# 13_Clocks.net
KiCad netlist of a schematic drawn in Altium Designer
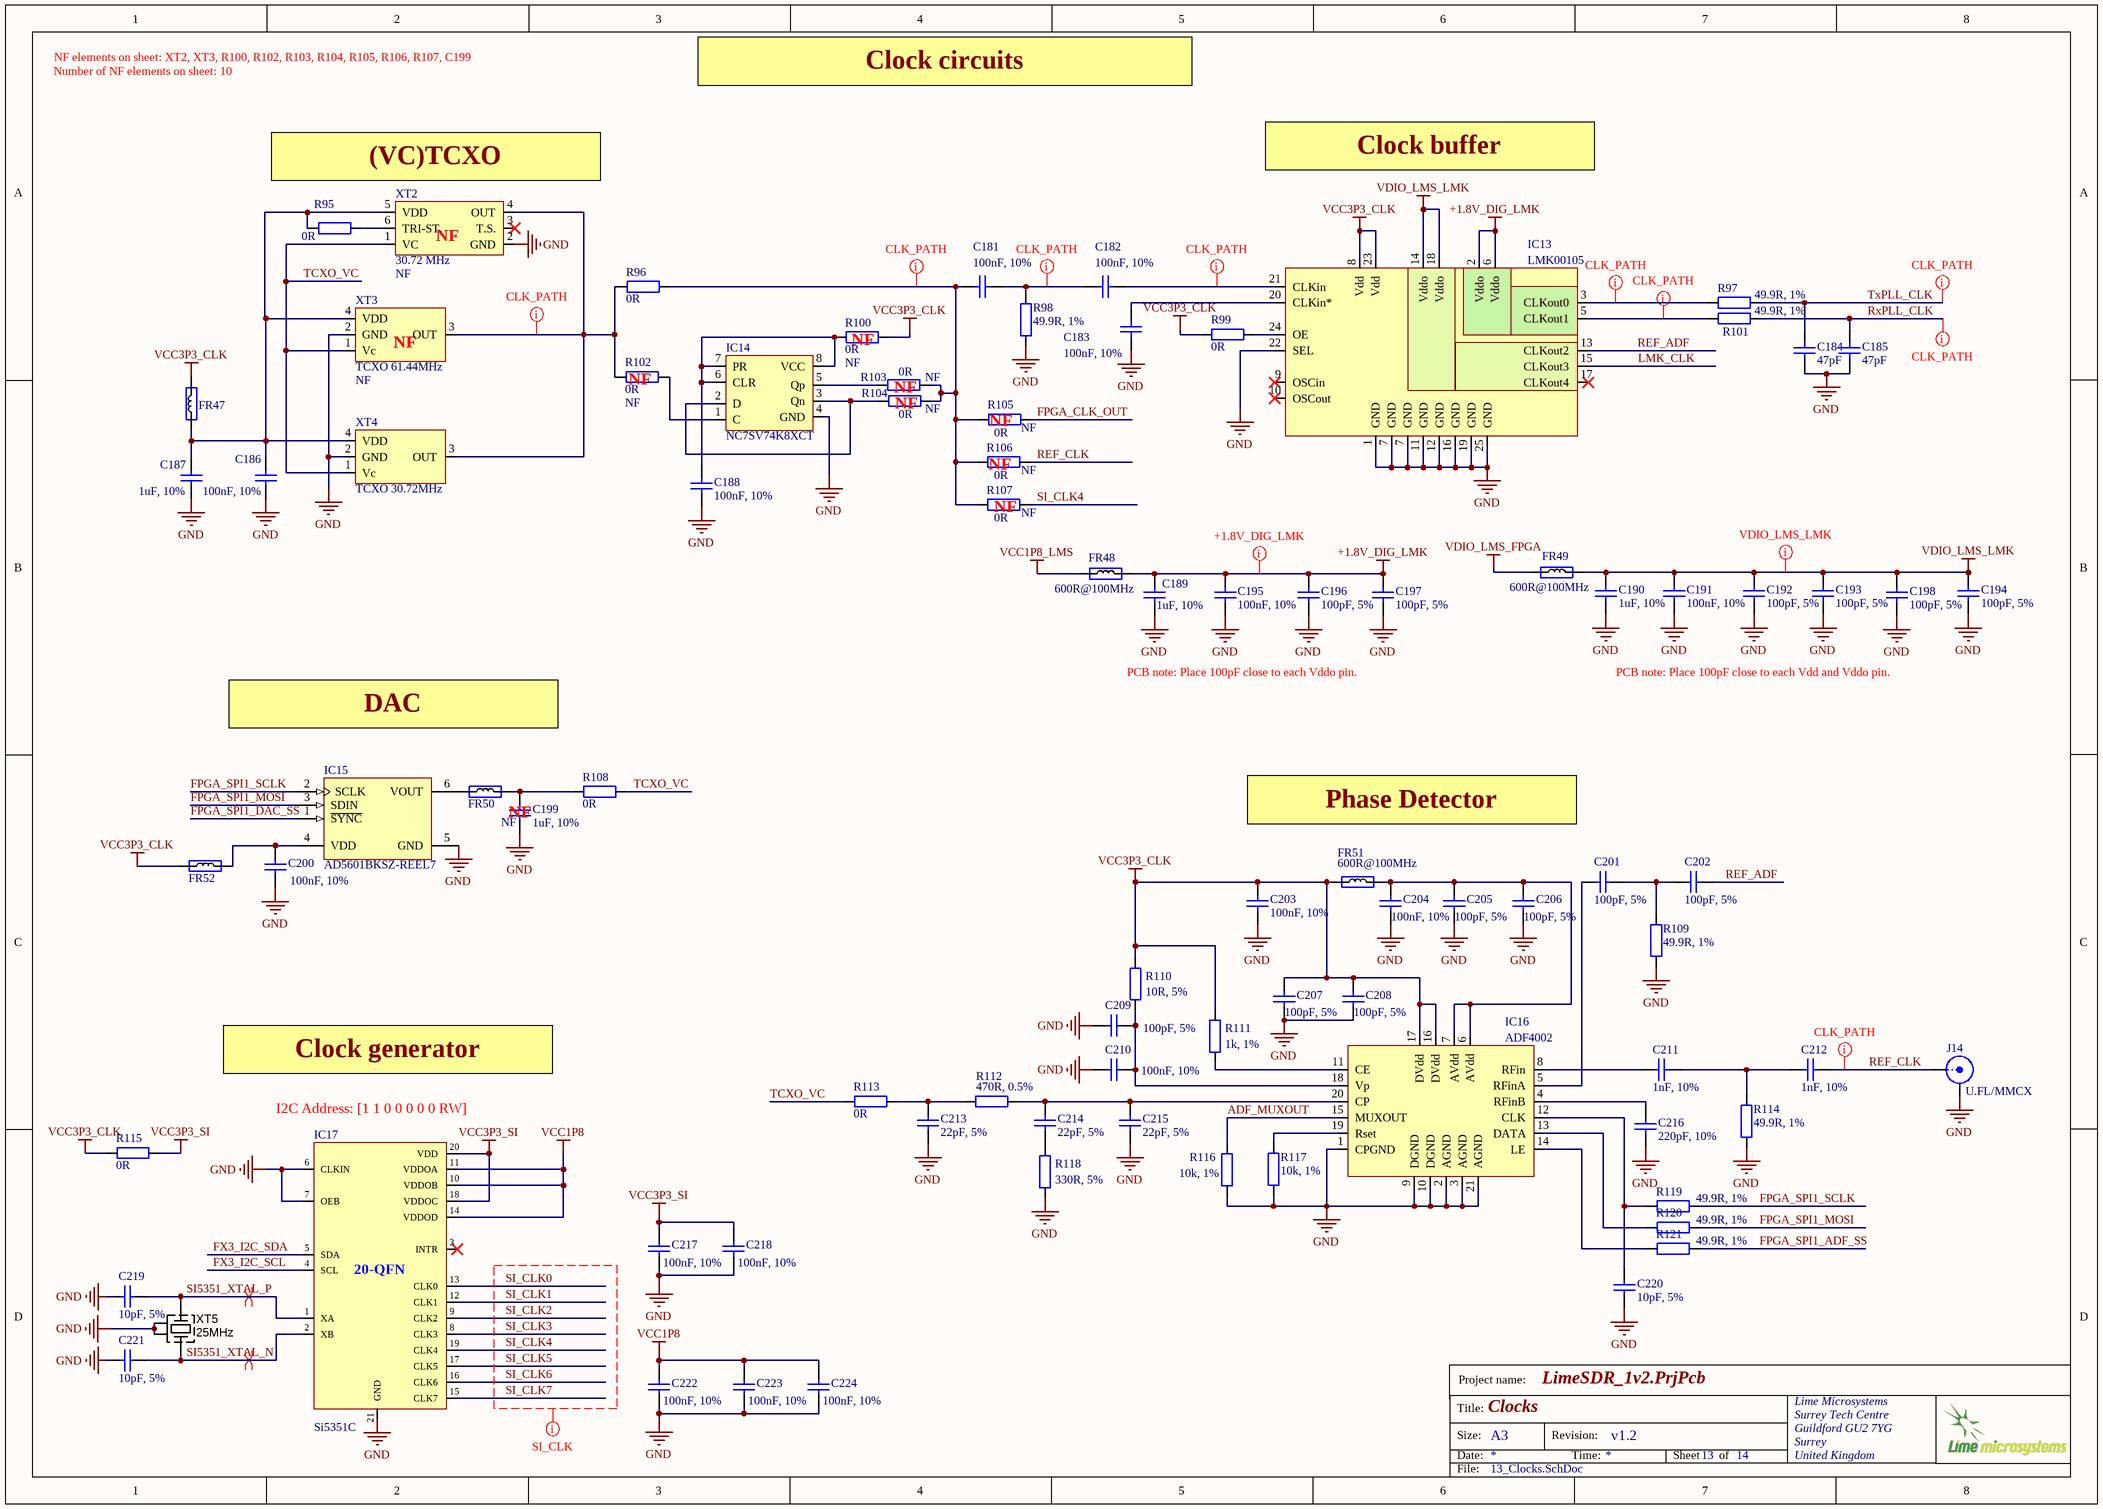
[diagram p0: 13_Clocks.SchDoc]

(export (version "E")
  (design (tool "Eeschema 10.0.6"))
  (components
    (comp (ref "C181")
      (value "100nF, 10%")
      (footprint "CAP0402")
      (fields
        (field (name "MANUFACTURER") "Murata Electronics")
        (field (name "TOLERANCE") "10 %")
        (field (name "MANUFACTURER PART NUMBER") "GRM155R71C104KA88D")
      )
      (libsource (lib "LimeMicroAltiumLib_schLib") (part "Cap_0402"))
    )
    (comp (ref "C182")
      (value "100nF, 10%")
      (footprint "CAP0402")
      (fields
        (field (name "MANUFACTURER") "Murata Electronics")
        (field (name "TOLERANCE") "10 %")
        (field (name "MANUFACTURER PART NUMBER") "GRM155R71C104KA88D")
      )
      (libsource (lib "LimeMicroAltiumLib_schLib") (part "Cap_0402"))
    )
    (comp (ref "C183")
      (value "100nF, 10%")
      (footprint "CAP0402")
      (fields
        (field (name "MANUFACTURER") "Murata Electronics")
        (field (name "TOLERANCE") "10 %")
        (field (name "MANUFACTURER PART NUMBER") "GRM155R71C104KA88D")
      )
      (libsource (lib "LimeMicroAltiumLib_schLib") (part "Cap_0402"))
    )
    (comp (ref "C184")
      (value "47pF")
      (footprint "CAP0402")
      (fields (field (name "TOLERANCE") "±1%") (field (name "MANUFACTURER") "TDK Corporation"))
      (libsource (lib "LimeMicroAltiumLib_schLib") (part "Cap_0402"))
    )
    (comp (ref "C185")
      (value "47pF")
      (footprint "CAP0402")
      (fields (field (name "TOLERANCE") "±1%") (field (name "MANUFACTURER") "TDK Corporation"))
      (libsource (lib "LimeMicroAltiumLib_schLib") (part "Cap_0402"))
    )
    (comp (ref "C186")
      (value "100nF, 10%")
      (footprint "CAP0402")
      (fields
        (field (name "MANUFACTURER") "Murata Electronics")
        (field (name "TOLERANCE") "10 %")
        (field (name "MANUFACTURER PART NUMBER") "GRM155R71C104KA88D")
      )
      (libsource (lib "LimeMicroAltiumLib_schLib") (part "Cap_0402"))
    )
    (comp (ref "C187")
      (value "1uF, 10%")
      (footprint "CAP0402")
      (fields (field (name "MANUFACTURER") "TDK"))
      (libsource (lib "LimeMicroAltiumLib_schLib") (part "Cap_0402"))
    )
    (comp (ref "C188")
      (value "100nF, 10%")
      (footprint "CAP0402")
      (fields
        (field (name "MANUFACTURER") "Murata Electronics")
        (field (name "TOLERANCE") "10 %")
        (field (name "MANUFACTURER PART NUMBER") "GRM155R71C104KA88D")
      )
      (libsource (lib "LimeMicroAltiumLib_schLib") (part "Cap_0402"))
    )
    (comp (ref "C189")
      (value "1uF, 10%")
      (footprint "CAP0402")
      (fields (field (name "MANUFACTURER") "TDK"))
      (libsource (lib "LimeMicroAltiumLib_schLib") (part "Cap_0402"))
    )
    (comp (ref "C190")
      (value "1uF, 10%")
      (footprint "CAP0402")
      (fields (field (name "MANUFACTURER") "TDK"))
      (libsource (lib "LimeMicroAltiumLib_schLib") (part "Cap_0402"))
    )
    (comp (ref "C191")
      (value "100nF, 10%")
      (footprint "CAP0402")
      (fields
        (field (name "MANUFACTURER") "Murata Electronics")
        (field (name "TOLERANCE") "10 %")
        (field (name "MANUFACTURER PART NUMBER") "GRM155R71C104KA88D")
      )
      (libsource (lib "LimeMicroAltiumLib_schLib") (part "Cap_0402"))
    )
    (comp (ref "C192")
      (value "100pF, 5%")
      (footprint "CAP0402")
      (fields (field (name "MANUFACTURER") "Yageo") (field (name "TOLERANCE") "±5%"))
      (libsource (lib "LimeMicroAltiumLib_schLib") (part "Cap_0402"))
    )
    (comp (ref "C193")
      (value "100pF, 5%")
      (footprint "CAP0402")
      (fields (field (name "MANUFACTURER") "Yageo") (field (name "TOLERANCE") "±5%"))
      (libsource (lib "LimeMicroAltiumLib_schLib") (part "Cap_0402"))
    )
    (comp (ref "C194")
      (value "100pF, 5%")
      (footprint "CAP0402")
      (fields (field (name "MANUFACTURER") "Yageo") (field (name "TOLERANCE") "±5%"))
      (libsource (lib "LimeMicroAltiumLib_schLib") (part "Cap_0402"))
    )
    (comp (ref "C195")
      (value "100nF, 10%")
      (footprint "CAP0402")
      (fields
        (field (name "MANUFACTURER") "Murata Electronics")
        (field (name "TOLERANCE") "10 %")
        (field (name "MANUFACTURER PART NUMBER") "GRM155R71C104KA88D")
      )
      (libsource (lib "LimeMicroAltiumLib_schLib") (part "Cap_0402"))
    )
    (comp (ref "C196")
      (value "100pF, 5%")
      (footprint "CAP0402")
      (fields (field (name "MANUFACTURER") "Yageo") (field (name "TOLERANCE") "±5%"))
      (libsource (lib "LimeMicroAltiumLib_schLib") (part "Cap_0402"))
    )
    (comp (ref "C197")
      (value "100pF, 5%")
      (footprint "CAP0402")
      (fields (field (name "MANUFACTURER") "Yageo") (field (name "TOLERANCE") "±5%"))
      (libsource (lib "LimeMicroAltiumLib_schLib") (part "Cap_0402"))
    )
    (comp (ref "C198")
      (value "100pF, 5%")
      (footprint "CAP0402")
      (fields (field (name "MANUFACTURER") "Yageo") (field (name "TOLERANCE") "±5%"))
      (libsource (lib "LimeMicroAltiumLib_schLib") (part "Cap_0402"))
    )
    (comp (ref "C199")
      (value "1uF, 10%")
      (footprint "CAP0402")
      (fields (field (name "ASSEMBLY INFO") "NF") (field (name "MANUFACTURER") "TDK"))
      (libsource (lib "LimeMicroAltiumLib_schLib") (part "Cap_0402"))
    )
    (comp (ref "C200")
      (value "100nF, 10%")
      (footprint "CAP0402")
      (fields
        (field (name "TOLERANCE") "10 %")
        (field (name "MANUFACTURER") "Murata Electronics")
        (field (name "MANUFACTURER PART NUMBER") "GRM155R71C104KA88D")
      )
      (libsource (lib "LimeFPGAboard_schLib") (part "Cap_0603"))
    )
    (comp (ref "C201")
      (value "100pF, 5%")
      (footprint "CAP0402")
      (fields (field (name "MANUFACTURER") "Yageo") (field (name "TOLERANCE") "±5%"))
      (libsource (lib "LimeMicroAltiumLib_schLib") (part "Cap_0402"))
    )
    (comp (ref "C202")
      (value "100pF, 5%")
      (footprint "CAP0402")
      (fields (field (name "MANUFACTURER") "Yageo") (field (name "TOLERANCE") "±5%"))
      (libsource (lib "LimeMicroAltiumLib_schLib") (part "Cap_0402"))
    )
    (comp (ref "C203")
      (value "100nF, 10%")
      (footprint "CAP0402")
      (fields
        (field (name "MANUFACTURER") "Murata Electronics")
        (field (name "TOLERANCE") "10 %")
        (field (name "MANUFACTURER PART NUMBER") "GRM155R71C104KA88D")
      )
      (libsource (lib "LimeMicroAltiumLib_schLib") (part "Cap_0402"))
    )
    (comp (ref "C204")
      (value "100nF, 10%")
      (footprint "CAP0402")
      (fields
        (field (name "MANUFACTURER") "Murata Electronics")
        (field (name "TOLERANCE") "10 %")
        (field (name "MANUFACTURER PART NUMBER") "GRM155R71C104KA88D")
      )
      (libsource (lib "LimeMicroAltiumLib_schLib") (part "Cap_0402"))
    )
    (comp (ref "C205")
      (value "100pF, 5%")
      (footprint "CAP0402")
      (fields (field (name "MANUFACTURER") "Yageo") (field (name "TOLERANCE") "±5%"))
      (libsource (lib "LimeMicroAltiumLib_schLib") (part "Cap_0402"))
    )
    (comp (ref "C206")
      (value "100pF, 5%")
      (footprint "CAP0402")
      (fields (field (name "MANUFACTURER") "Yageo") (field (name "TOLERANCE") "±5%"))
      (libsource (lib "LimeMicroAltiumLib_schLib") (part "Cap_0402"))
    )
    (comp (ref "C207")
      (value "100pF, 5%")
      (footprint "CAP0402")
      (fields (field (name "MANUFACTURER") "Yageo") (field (name "TOLERANCE") "±5%"))
      (libsource (lib "LimeMicroAltiumLib_schLib") (part "Cap_0402"))
    )
    (comp (ref "C208")
      (value "100pF, 5%")
      (footprint "CAP0402")
      (fields (field (name "MANUFACTURER") "Yageo") (field (name "TOLERANCE") "±5%"))
      (libsource (lib "LimeMicroAltiumLib_schLib") (part "Cap_0402"))
    )
    (comp (ref "C209")
      (value "100pF, 5%")
      (footprint "CAP0402")
      (fields (field (name "MANUFACTURER") "Yageo") (field (name "TOLERANCE") "±5%"))
      (libsource (lib "LimeMicroAltiumLib_schLib") (part "Cap_0402"))
    )
    (comp (ref "C210")
      (value "100nF, 10%")
      (footprint "CAP0402")
      (fields
        (field (name "MANUFACTURER") "Murata Electronics")
        (field (name "TOLERANCE") "10 %")
        (field (name "MANUFACTURER PART NUMBER") "GRM155R71C104KA88D")
      )
      (libsource (lib "LimeMicroAltiumLib_schLib") (part "Cap_0402"))
    )
    (comp (ref "C211")
      (value "1nF, 10%")
      (footprint "CAP0402")
      (fields (field (name "TOLERANCE") "10 %") (field (name "MANUFACTURER") "Murata Electronics"))
      (libsource (lib "LimeMicroAltiumLib_schLib") (part "Cap_0402"))
    )
    (comp (ref "C212")
      (value "1nF, 10%")
      (footprint "CAP0402")
      (fields (field (name "TOLERANCE") "10 %") (field (name "MANUFACTURER") "Murata Electronics"))
      (libsource (lib "LimeMicroAltiumLib_schLib") (part "Cap_0402"))
    )
    (comp (ref "C213")
      (value "22pF, 5%")
      (footprint "CAP0402")
      (fields (field (name "TOLERANCE") "±5%") (field (name "MANUFACTURER") "Yageo"))
      (libsource (lib "LimeMicroAltiumLib_schLib") (part "Cap_0402"))
    )
    (comp (ref "C214")
      (value "22pF, 5%")
      (footprint "CAP0402")
      (fields (field (name "TOLERANCE") "±5%") (field (name "MANUFACTURER") "Yageo"))
      (libsource (lib "LimeMicroAltiumLib_schLib") (part "Cap_0402"))
    )
    (comp (ref "C215")
      (value "22pF, 5%")
      (footprint "CAP0402")
      (fields (field (name "TOLERANCE") "±5%") (field (name "MANUFACTURER") "Yageo"))
      (libsource (lib "LimeMicroAltiumLib_schLib") (part "Cap_0402"))
    )
    (comp (ref "C216")
      (value "220pF, 10%")
      (footprint "CAP0402")
      (fields (field (name "MANUFACTURER") "Yageo") (field (name "TOLERANCE") "±10%"))
      (libsource (lib "LimeMicroAltiumLib_schLib") (part "Cap_0402"))
    )
    (comp (ref "C217")
      (value "100nF, 10%")
      (footprint "CAP0402")
      (fields
        (field (name "TOLERANCE") "10 %")
        (field (name "MANUFACTURER") "Murata Electronics")
        (field (name "MANUFACTURER PART NUMBER") "GRM155R71C104KA88D")
      )
      (libsource (lib "LimeFPGAboard_schLib") (part "Cap_0603"))
    )
    (comp (ref "C218")
      (value "100nF, 10%")
      (footprint "CAP0402")
      (fields
        (field (name "TOLERANCE") "10 %")
        (field (name "MANUFACTURER") "Murata Electronics")
        (field (name "MANUFACTURER PART NUMBER") "GRM155R71C104KA88D")
      )
      (libsource (lib "LimeFPGAboard_schLib") (part "Cap_0603"))
    )
    (comp (ref "C219")
      (value "10pF, 5%")
      (footprint "CAP0402")
      (fields (field (name "MANUFACTURER") "AVX"))
      (libsource (lib "LimeFPGAboard_schLib") (part "Cap_0402"))
    )
    (comp (ref "C220")
      (value "10pF, 5%")
      (footprint "CAP0402")
      (fields (field (name "MANUFACTURER") "AVX"))
      (libsource (lib "LimeMicroAltiumLib_schLib") (part "Cap_0402"))
    )
    (comp (ref "C221")
      (value "10pF, 5%")
      (footprint "CAP0402")
      (fields (field (name "MANUFACTURER") "AVX"))
      (libsource (lib "LimeFPGAboard_schLib") (part "Cap_0402"))
    )
    (comp (ref "C222")
      (value "100nF, 10%")
      (footprint "CAP0402")
      (fields
        (field (name "TOLERANCE") "10 %")
        (field (name "MANUFACTURER") "Murata Electronics")
        (field (name "MANUFACTURER PART NUMBER") "GRM155R71C104KA88D")
      )
      (libsource (lib "LimeFPGAboard_schLib") (part "Cap_0603"))
    )
    (comp (ref "C223")
      (value "100nF, 10%")
      (footprint "CAP0402")
      (fields
        (field (name "TOLERANCE") "10 %")
        (field (name "MANUFACTURER") "Murata Electronics")
        (field (name "MANUFACTURER PART NUMBER") "GRM155R71C104KA88D")
      )
      (libsource (lib "LimeFPGAboard_schLib") (part "Cap_0603"))
    )
    (comp (ref "C224")
      (value "100nF, 10%")
      (footprint "CAP0402")
      (fields
        (field (name "TOLERANCE") "10 %")
        (field (name "MANUFACTURER") "Murata Electronics")
        (field (name "MANUFACTURER PART NUMBER") "GRM155R71C104KA88D")
      )
      (libsource (lib "LimeFPGAboard_schLib") (part "Cap_0603"))
    )
    (comp (ref "FR47")
      (value "Ferrite")
      (footprint "RES0201")
      (fields (field (name "MANUFACTURER") "Taiyo Yuden"))
      (libsource (lib "LimeMicroAltiumLib_schLib") (part "Ferrite"))
    )
    (comp (ref "FR48")
      (value "600R@100MHz")
      (footprint "RES0805")
      (fields (field (name "MANUFACTURER") "TDK Corporation"))
      (libsource (lib "LimeMicroAltiumLib_schLib") (part "Ferrite"))
    )
    (comp (ref "FR49")
      (value "600R@100MHz")
      (footprint "RES0805")
      (fields (field (name "MANUFACTURER") "TDK Corporation"))
      (libsource (lib "LimeMicroAltiumLib_schLib") (part "Ferrite"))
    )
    (comp (ref "FR50")
      (value "Ferrite")
      (footprint "RES0201")
      (fields (field (name "MANUFACTURER") "Taiyo Yuden"))
      (libsource (lib "LimeMicroAltiumLib_schLib") (part "Ferrite"))
    )
    (comp (ref "FR51")
      (value "600R@100MHz")
      (footprint "RES0805")
      (fields (field (name "MANUFACTURER") "TDK Corporation"))
      (libsource (lib "LimeMicroAltiumLib_schLib") (part "Ferrite"))
    )
    (comp (ref "FR52")
      (value "Ferrite")
      (footprint "RES0201")
      (fields (field (name "MANUFACTURER") "Taiyo Yuden"))
      (libsource (lib "LimeMicroAltiumLib_schLib") (part "Ferrite"))
    )
    (comp (ref "IC13")
      (value "LMK00105")
      (footprint "LMK00105SQ")
      (fields (field (name "MANUFACTURER") "Texas Instruments"))
      (libsource (lib "LimeMicroAltiumLib_schLib") (part "LMK00105"))
    )
    (comp (ref "IC14")
      (value "NC7SV74K8XCT")
      (footprint "NC7SV74K8XCT")
      (fields (field (name "MANUFACTURER") "Fairchild Semiconductor"))
      (libsource (lib "LimeMicroAltiumLib_schLib") (part "NC7SV74K8XCT"))
    )
    (comp (ref "IC15")
      (value "AD5601BKSZ-REEL7")
      (footprint "AD5601_SOT23-6")
      (fields (field (name "GENERIC PART NUMBER") "AD5601") (field (name "MANUFACTURER") "Analog Devices"))
      (libsource (lib "LimeMicroAltiumLib_schLib") (part "AD5601BKSZ-REEL7"))
    )
    (comp (ref "IC16")
      (value "ADF4002")
      (footprint "ADF4002")
      (fields (field (name "MANUFACTURER") "Analog Devices Inc"))
      (libsource (lib "LimeMicroAltiumLib_schLib") (part "ADF4002"))
    )
    (comp (ref "IC17")
      (value "Si5351C")
      (footprint "Si5351C_20QFN")
      (fields (field (name "MANUFACTURER") "Silicon Labs"))
      (libsource (lib "LimeFPGAboard_schLib") (part "Si5351C"))
    )
    (comp (ref "J14")
      (value "U.FL/MMCX")
      (footprint "MMCX_UFL_conn_u")
      (fields (field (name "MANUFACTURER") "Molex, LLC"))
      (libsource (lib "LimeMicroAltiumLib_schLib") (part "RF_IF_connector"))
    )
    (comp (ref "R95")
      (value "0R")
      (footprint "RES0402")
      (fields (field (name "MANUFACTURER") "Yageo") (field (name "TOLERANCE") "Jumper"))
      (libsource (lib "LimeMicroAltiumLib_schLib") (part "Res_0402"))
    )
    (comp (ref "R96")
      (value "0R")
      (footprint "RES0402")
      (fields (field (name "MANUFACTURER") "Yageo") (field (name "TOLERANCE") "Jumper"))
      (libsource (lib "LimeMicroAltiumLib_schLib") (part "Res_0402"))
    )
    (comp (ref "R97")
      (value "49.9R, 1%")
      (footprint "LimeMicroAltiumLib_pcbLib:RES0402")
      (fields
        (field (name "TOLERANCE") "±1%")
        (field (name "MANUFACTURER") "Samsung Electro-Mechanics America, Inc.")
        (field (name "MANUFACTURER PART NUMBER") "RC1005F49R9CS")
      )
      (libsource (lib "LimeMicroAltiumLib_schLib") (part "Res_0402"))
    )
    (comp (ref "R98")
      (value "49.9R, 1%")
      (footprint "LimeMicroAltiumLib_pcbLib:RES0402")
      (fields
        (field (name "TOLERANCE") "±1%")
        (field (name "MANUFACTURER") "Samsung Electro-Mechanics America, Inc.")
        (field (name "MANUFACTURER PART NUMBER") "RC1005F49R9CS")
      )
      (libsource (lib "LimeMicroAltiumLib_schLib") (part "Res_0402"))
    )
    (comp (ref "R99")
      (value "0R")
      (footprint "RES0402")
      (fields (field (name "MANUFACTURER") "Yageo") (field (name "TOLERANCE") "Jumper"))
      (libsource (lib "LimeMicroAltiumLib_schLib") (part "Res_0402"))
    )
    (comp (ref "R100")
      (value "0R")
      (footprint "RES0402")
      (fields
        (field (name "ASSEMBLY INFO") "NF")
        (field (name "MANUFACTURER") "Yageo")
        (field (name "TOLERANCE") "Jumper")
      )
      (libsource (lib "LimeMicroAltiumLib_schLib") (part "Res_0402"))
    )
    (comp (ref "R101")
      (value "49.9R, 1%")
      (footprint "LimeMicroAltiumLib_pcbLib:RES0402")
      (fields
        (field (name "TOLERANCE") "±1%")
        (field (name "MANUFACTURER") "Samsung Electro-Mechanics America, Inc.")
        (field (name "MANUFACTURER PART NUMBER") "RC1005F49R9CS")
      )
      (libsource (lib "LimeMicroAltiumLib_schLib") (part "Res_0402"))
    )
    (comp (ref "R102")
      (value "0R")
      (footprint "RES0402")
      (fields
        (field (name "ASSEMBLY INFO") "NF")
        (field (name "MANUFACTURER") "Yageo")
        (field (name "TOLERANCE") "Jumper")
      )
      (libsource (lib "LimeMicroAltiumLib_schLib") (part "Res_0402"))
    )
    (comp (ref "R103")
      (value "0R")
      (footprint "RES0402")
      (fields
        (field (name "ASSEMBLY INFO") "NF")
        (field (name "MANUFACTURER") "Yageo")
        (field (name "TOLERANCE") "Jumper")
      )
      (libsource (lib "LimeMicroAltiumLib_schLib") (part "Res_0402"))
    )
    (comp (ref "R104")
      (value "0R")
      (footprint "RES0402")
      (fields
        (field (name "ASSEMBLY INFO") "NF")
        (field (name "MANUFACTURER") "Yageo")
        (field (name "TOLERANCE") "Jumper")
      )
      (libsource (lib "LimeMicroAltiumLib_schLib") (part "Res_0402"))
    )
    (comp (ref "R105")
      (value "0R")
      (footprint "RES0402")
      (fields
        (field (name "ASSEMBLY INFO") "NF")
        (field (name "MANUFACTURER") "Yageo")
        (field (name "TOLERANCE") "Jumper")
      )
      (libsource (lib "LimeMicroAltiumLib_schLib") (part "Res_0402"))
    )
    (comp (ref "R106")
      (value "0R")
      (footprint "RES0402")
      (fields
        (field (name "ASSEMBLY INFO") "NF")
        (field (name "MANUFACTURER") "Yageo")
        (field (name "TOLERANCE") "Jumper")
      )
      (libsource (lib "LimeMicroAltiumLib_schLib") (part "Res_0402"))
    )
    (comp (ref "R107")
      (value "0R")
      (footprint "RES0402")
      (fields
        (field (name "ASSEMBLY INFO") "NF")
        (field (name "MANUFACTURER") "Yageo")
        (field (name "TOLERANCE") "Jumper")
      )
      (libsource (lib "LimeMicroAltiumLib_schLib") (part "Res_0402"))
    )
    (comp (ref "R108")
      (value "0R")
      (footprint "RES0402")
      (fields (field (name "MANUFACTURER") "Yageo") (field (name "TOLERANCE") "Jumper"))
      (libsource (lib "LimeMicroAltiumLib_schLib") (part "Res_0402"))
    )
    (comp (ref "R109")
      (value "49.9R, 1%")
      (footprint "LimeMicroAltiumLib_pcbLib:RES0402")
      (fields
        (field (name "TOLERANCE") "±1%")
        (field (name "MANUFACTURER") "Samsung Electro-Mechanics America, Inc.")
        (field (name "MANUFACTURER PART NUMBER") "RC1005F49R9CS")
      )
      (libsource (lib "LimeMicroAltiumLib_schLib") (part "Res_0402"))
    )
    (comp (ref "R110")
      (value "10R, 5%")
      (footprint "RES0402")
      (fields (field (name "TOLERANCE") "±5%") (field (name "MANUFACTURER") "Yageo"))
      (libsource (lib "LimeMicroAltiumLib_schLib") (part "Res_0402"))
    )
    (comp (ref "R111")
      (value "1k, 1%")
      (footprint "RES0402")
      (fields (field (name "MANUFACTURER") "Stackpole Electronics Inc") (field (name "TOLERANCE") "±1%"))
      (libsource (lib "LimeMicroAltiumLib_schLib") (part "Res_0402"))
    )
    (comp (ref "R112")
      (value "470R, 0.5%")
      (footprint "RES0402")
      (fields
        (field (name "TOLERANCE") "±0.5%")
        (field (name "MANUFACTURER") "Panasonic Electronic Components")
      )
      (libsource (lib "LimeMicroAltiumLib_schLib") (part "Res_0402"))
    )
    (comp (ref "R113")
      (value "0R")
      (footprint "RES0402")
      (fields (field (name "MANUFACTURER") "Yageo") (field (name "TOLERANCE") "Jumper"))
      (libsource (lib "LimeMicroAltiumLib_schLib") (part "Res_0402"))
    )
    (comp (ref "R114")
      (value "49.9R, 1%")
      (footprint "LimeMicroAltiumLib_pcbLib:RES0402")
      (fields
        (field (name "TOLERANCE") "±1%")
        (field (name "MANUFACTURER") "Samsung Electro-Mechanics America, Inc.")
        (field (name "MANUFACTURER PART NUMBER") "RC1005F49R9CS")
      )
      (libsource (lib "LimeMicroAltiumLib_schLib") (part "Res_0402"))
    )
    (comp (ref "R115")
      (value "0R")
      (footprint "RES0402")
      (fields (field (name "MANUFACTURER") "Yageo") (field (name "TOLERANCE") "Jumper"))
      (libsource (lib "LimeMicroAltiumLib_schLib") (part "Res_0402"))
    )
    (comp (ref "R116")
      (value "10k, 1%")
      (footprint "RES0402")
      (fields (field (name "MANUFACTURER") "Yageo") (field (name "TOLERANCE") "±1%"))
      (libsource (lib "LimeMicroAltiumLib_schLib") (part "Res_0402"))
    )
    (comp (ref "R117")
      (value "10k, 1%")
      (footprint "RES0402")
      (fields (field (name "MANUFACTURER") "Yageo") (field (name "TOLERANCE") "±1%"))
      (libsource (lib "LimeMicroAltiumLib_schLib") (part "Res_0402"))
    )
    (comp (ref "R118")
      (value "330R, 5%")
      (footprint "RES0402")
      (fields (field (name "MANUFACTURER") "Yageo") (field (name "TOLERANCE") "±5%"))
      (libsource (lib "LimeMicroAltiumLib_schLib") (part "Res_0402"))
    )
    (comp (ref "R119")
      (value "49.9R, 1%")
      (footprint "LimeMicroAltiumLib_pcbLib:RES0402")
      (fields
        (field (name "TOLERANCE") "±1%")
        (field (name "MANUFACTURER") "Samsung Electro-Mechanics America, Inc.")
        (field (name "MANUFACTURER PART NUMBER") "RC1005F49R9CS")
      )
      (libsource (lib "LimeMicroAltiumLib_schLib") (part "Res_0402"))
    )
    (comp (ref "R120")
      (value "49.9R, 1%")
      (footprint "LimeMicroAltiumLib_pcbLib:RES0402")
      (fields
        (field (name "TOLERANCE") "±1%")
        (field (name "MANUFACTURER") "Samsung Electro-Mechanics America, Inc.")
        (field (name "MANUFACTURER PART NUMBER") "RC1005F49R9CS")
      )
      (libsource (lib "LimeMicroAltiumLib_schLib") (part "Res_0402"))
    )
    (comp (ref "R121")
      (value "49.9R, 1%")
      (footprint "LimeMicroAltiumLib_pcbLib:RES0402")
      (fields
        (field (name "TOLERANCE") "±1%")
        (field (name "MANUFACTURER") "Samsung Electro-Mechanics America, Inc.")
        (field (name "MANUFACTURER PART NUMBER") "RC1005F49R9CS")
      )
      (libsource (lib "LimeMicroAltiumLib_schLib") (part "Res_0402"))
    )
    (comp (ref "XT2")
      (value "30.72 MHz")
      (footprint "RAKON_RPT7050A")
      (fields (field (name "ASSEMBLY INFO") "NF") (field (name "MANUFACTURER") "Rakon"))
      (libsource (lib "LimeMicroAltiumLib_schLib") (part "RPT7050A"))
    )
    (comp (ref "XT3")
      (value "TCXO 61.44MHz")
      (footprint "RAKON_TXCO_61MHz_v2")
      (fields (field (name "ASSEMBLY INFO") "NF") (field (name "MANUFACTURER") "Rakon"))
      (libsource (lib "LimeMicroAltiumLib_schLib") (part "TXCO"))
    )
    (comp (ref "XT4")
      (value "TCXO 30.72MHz")
      (footprint "RAKON_TXCO")
      (fields (field (name "MANUFACTURER") "Rakon"))
      (libsource (lib "LimeMicroAltiumLib_schLib") (part "TXCO"))
    )
    (comp (ref "XT5")
      (value "25MHz")
      (footprint "CRYSTAL_4-LCC")
      (description "Oscillator Crystal 25 MHz")
      (fields (field (name "MANUFACTURER") "ABRACON"))
      (libsource (lib "LimeFPGAboard_schLib") (part "CRYSTAL_19M2"))
    )
  )
  (nets
    (net (code "1") (name "+1.8V_DIG_LMK") (class "Default")
      (node (ref "C189") (pin "2") (pinfunction "2_2") (pintype "passive"))
      (node (ref "C195") (pin "2") (pinfunction "2_2") (pintype "passive"))
      (node (ref "C196") (pin "2") (pinfunction "2_2") (pintype "passive"))
      (node (ref "C197") (pin "2") (pinfunction "2_2") (pintype "passive"))
      (node (ref "FR48") (pin "2") (pinfunction "2_2") (pintype "passive"))
      (node (ref "IC13") (pin "2") (pinfunction "Vddo_2") (pintype "passive"))
      (node (ref "IC13") (pin "6") (pinfunction "Vddo_6") (pintype "passive"))
    )
    (net (code "2") (name "/ADF_MUXOUT") (class "Default")
      (node (ref "IC16") (pin "15") (pinfunction "MUXOUT_15") (pintype "passive"))
      (node (ref "R116") (pin "1") (pinfunction "1_1") (pintype "passive"))
    )
    (net (code "3") (name "/FPGA_CLK_OUT") (class "Default")
      (node (ref "R105") (pin "1") (pinfunction "1_1") (pintype "passive"))
    )
    (net (code "4") (name "/FPGA_SPI1_ADF_SS") (class "Default")
      (node (ref "R121") (pin "1") (pinfunction "1_1") (pintype "passive"))
    )
    (net (code "5") (name "/FPGA_SPI1_DAC_SS") (class "Default")
      (node (ref "IC15") (pin "1") (pinfunction "~{SYNC}_1") (pintype "input"))
    )
    (net (code "6") (name "/FPGA_SPI1_MOSI") (class "Default")
      (node (ref "IC15") (pin "3") (pinfunction "SDIN_3") (pintype "input"))
      (node (ref "R120") (pin "1") (pinfunction "1_1") (pintype "passive"))
    )
    (net (code "7") (name "/FPGA_SPI1_SCLK") (class "Default")
      (node (ref "IC15") (pin "2") (pinfunction "SCLK_2") (pintype "input"))
      (node (ref "R119") (pin "1") (pinfunction "1_1") (pintype "passive"))
    )
    (net (code "8") (name "/FX3_I2C_SCL") (class "Default")
      (node (ref "IC17") (pin "4") (pinfunction "SCL_4") (pintype "passive"))
    )
    (net (code "9") (name "/FX3_I2C_SDA") (class "Default")
      (node (ref "IC17") (pin "5") (pinfunction "SDA_5") (pintype "passive"))
    )
    (net (code "10") (name "/LMK_CLK") (class "Default")
      (node (ref "IC13") (pin "15") (pinfunction "CLKout3_15") (pintype "passive"))
    )
    (net (code "11") (name "/REF_ADF") (class "Default")
      (node (ref "C202") (pin "2") (pinfunction "2_2") (pintype "passive"))
      (node (ref "IC13") (pin "13") (pinfunction "CLKout2_13") (pintype "passive"))
    )
    (net (code "12") (name "/REF_CLK") (class "Default")
      (node (ref "C212") (pin "1") (pinfunction "1_1") (pintype "passive"))
      (node (ref "J14") (pin "1") (pinfunction "X_1") (pintype "passive"))
      (node (ref "R106") (pin "2") (pinfunction "2_2") (pintype "passive"))
    )
    (net (code "13") (name "/RxPLL_CLK") (class "Default")
      (node (ref "C185") (pin "2") (pinfunction "2_2") (pintype "passive"))
      (node (ref "R101") (pin "1") (pinfunction "1_1") (pintype "passive"))
    )
    (net (code "14") (name "/SI5351_XTAL_N") (class "Default")
      (node (ref "C221") (pin "2") (pinfunction "2_2") (pintype "passive"))
      (node (ref "IC17") (pin "2") (pinfunction "XB_2") (pintype "passive"))
      (node (ref "XT5") (pin "3") (pinfunction "X_3") (pintype "passive"))
    )
    (net (code "15") (name "/SI5351_XTAL_P") (class "Default")
      (node (ref "C219") (pin "2") (pinfunction "2_2") (pintype "passive"))
      (node (ref "IC17") (pin "1") (pinfunction "XA_1") (pintype "passive"))
      (node (ref "XT5") (pin "1") (pinfunction "X_1") (pintype "passive"))
    )
    (net (code "16") (name "/SI_CLK0") (class "Default")
      (node (ref "IC17") (pin "13") (pinfunction "CLK0_13") (pintype "passive"))
    )
    (net (code "17") (name "/SI_CLK1") (class "Default")
      (node (ref "IC17") (pin "12") (pinfunction "CLK1_12") (pintype "passive"))
    )
    (net (code "18") (name "/SI_CLK2") (class "Default")
      (node (ref "IC17") (pin "9") (pinfunction "CLK2_9") (pintype "passive"))
    )
    (net (code "19") (name "/SI_CLK3") (class "Default")
      (node (ref "IC17") (pin "8") (pinfunction "CLK3_8") (pintype "passive"))
    )
    (net (code "20") (name "/SI_CLK4") (class "Default")
      (node (ref "IC17") (pin "19") (pinfunction "CLK4_19") (pintype "passive"))
      (node (ref "R107") (pin "2") (pinfunction "2_2") (pintype "passive"))
    )
    (net (code "21") (name "/SI_CLK5") (class "Default")
      (node (ref "IC17") (pin "17") (pinfunction "CLK5_17") (pintype "passive"))
    )
    (net (code "22") (name "/SI_CLK6") (class "Default")
      (node (ref "IC17") (pin "16") (pinfunction "CLK6_16") (pintype "passive"))
    )
    (net (code "23") (name "/SI_CLK7") (class "Default")
      (node (ref "IC17") (pin "15") (pinfunction "CLK7_15") (pintype "passive"))
    )
    (net (code "24") (name "/TCXO_VC") (class "Default")
      (node (ref "R108") (pin "1") (pinfunction "1_1") (pintype "passive"))
      (node (ref "R113") (pin "2") (pinfunction "2_2") (pintype "passive"))
      (node (ref "XT2") (pin "1") (pinfunction "VC_1") (pintype "passive"))
      (node (ref "XT3") (pin "1") (pinfunction "Vc_1") (pintype "passive"))
      (node (ref "XT4") (pin "1") (pinfunction "Vc_1") (pintype "passive"))
    )
    (net (code "25") (name "/TxPLL_CLK") (class "Default")
      (node (ref "C184") (pin "2") (pinfunction "2_2") (pintype "passive"))
      (node (ref "R97") (pin "1") (pinfunction "1_1") (pintype "passive"))
    )
    (net (code "26") (name "GND") (class "Default")
      (node (ref "C183") (pin "1") (pinfunction "1_1") (pintype "passive"))
      (node (ref "C184") (pin "1") (pinfunction "1_1") (pintype "passive"))
      (node (ref "C185") (pin "1") (pinfunction "1_1") (pintype "passive"))
      (node (ref "C186") (pin "1") (pinfunction "1_1") (pintype "passive"))
      (node (ref "C187") (pin "1") (pinfunction "1_1") (pintype "passive"))
      (node (ref "C188") (pin "1") (pinfunction "1_1") (pintype "passive"))
      (node (ref "C189") (pin "1") (pinfunction "1_1") (pintype "passive"))
      (node (ref "C190") (pin "1") (pinfunction "1_1") (pintype "passive"))
      (node (ref "C191") (pin "1") (pinfunction "1_1") (pintype "passive"))
      (node (ref "C192") (pin "1") (pinfunction "1_1") (pintype "passive"))
      (node (ref "C193") (pin "1") (pinfunction "1_1") (pintype "passive"))
      (node (ref "C194") (pin "1") (pinfunction "1_1") (pintype "passive"))
      (node (ref "C195") (pin "1") (pinfunction "1_1") (pintype "passive"))
      (node (ref "C196") (pin "1") (pinfunction "1_1") (pintype "passive"))
      (node (ref "C197") (pin "1") (pinfunction "1_1") (pintype "passive"))
      (node (ref "C198") (pin "1") (pinfunction "1_1") (pintype "passive"))
      (node (ref "C199") (pin "1") (pinfunction "1_1") (pintype "passive"))
      (node (ref "C200") (pin "2") (pinfunction "2_2") (pintype "passive"))
      (node (ref "C203") (pin "1") (pinfunction "1_1") (pintype "passive"))
      (node (ref "C204") (pin "1") (pinfunction "1_1") (pintype "passive"))
      (node (ref "C205") (pin "2") (pinfunction "2_2") (pintype "passive"))
      (node (ref "C206") (pin "2") (pinfunction "2_2") (pintype "passive"))
      (node (ref "C207") (pin "2") (pinfunction "2_2") (pintype "passive"))
      (node (ref "C208") (pin "2") (pinfunction "2_2") (pintype "passive"))
      (node (ref "C209") (pin "1") (pinfunction "1_1") (pintype "passive"))
      (node (ref "C210") (pin "2") (pinfunction "2_2") (pintype "passive"))
      (node (ref "C213") (pin "1") (pinfunction "1_1") (pintype "passive"))
      (node (ref "C215") (pin "1") (pinfunction "1_1") (pintype "passive"))
      (node (ref "C216") (pin "2") (pinfunction "2_2") (pintype "passive"))
      (node (ref "C217") (pin "2") (pinfunction "2_2") (pintype "passive"))
      (node (ref "C218") (pin "2") (pinfunction "2_2") (pintype "passive"))
      (node (ref "C219") (pin "1") (pinfunction "1_1") (pintype "passive"))
      (node (ref "C220") (pin "1") (pinfunction "1_1") (pintype "passive"))
      (node (ref "C221") (pin "1") (pinfunction "1_1") (pintype "passive"))
      (node (ref "C222") (pin "2") (pinfunction "2_2") (pintype "passive"))
      (node (ref "C223") (pin "2") (pinfunction "2_2") (pintype "passive"))
      (node (ref "C224") (pin "2") (pinfunction "2_2") (pintype "passive"))
      (node (ref "IC13") (pin "1") (pinfunction "GND_1") (pintype "passive"))
      (node (ref "IC13") (pin "11") (pinfunction "GND_11") (pintype "passive"))
      (node (ref "IC13") (pin "12") (pinfunction "GND_12") (pintype "passive"))
      (node (ref "IC13") (pin "16") (pinfunction "GND_16") (pintype "passive"))
      (node (ref "IC13") (pin "19") (pinfunction "GND_19") (pintype "passive"))
      (node (ref "IC13") (pin "22") (pinfunction "SEL_22") (pintype "passive"))
      (node (ref "IC13") (pin "25") (pinfunction "GND_25") (pintype "passive"))
      (node (ref "IC13") (pin "7") (pinfunction "GND_7") (pintype "passive"))
      (node (ref "IC14") (pin "4") (pinfunction "GND_4") (pintype "passive"))
      (node (ref "IC15") (pin "5") (pinfunction "GND_5") (pintype "power_in"))
      (node (ref "IC16") (pin "1") (pinfunction "CPGND_1") (pintype "passive"))
      (node (ref "IC16") (pin "10") (pinfunction "DGND_10") (pintype "passive"))
      (node (ref "IC16") (pin "2") (pinfunction "AGND_2") (pintype "passive"))
      (node (ref "IC16") (pin "21") (pinfunction "AGND_21") (pintype "passive"))
      (node (ref "IC16") (pin "3") (pinfunction "AGND_3") (pintype "passive"))
      (node (ref "IC16") (pin "9") (pinfunction "DGND_9") (pintype "passive"))
      (node (ref "IC17") (pin "21") (pinfunction "GND_21") (pintype "passive"))
      (node (ref "IC17") (pin "6") (pinfunction "CLKIN_6") (pintype "passive"))
      (node (ref "IC17") (pin "7") (pinfunction "OEB_7") (pintype "passive"))
      (node (ref "J14") (pin "2") (pinfunction "Y_2") (pintype "passive"))
      (node (ref "R109") (pin "1") (pinfunction "1_1") (pintype "passive"))
      (node (ref "R114") (pin "1") (pinfunction "1_1") (pintype "passive"))
      (node (ref "R116") (pin "2") (pinfunction "2_2") (pintype "passive"))
      (node (ref "R117") (pin "2") (pinfunction "2_2") (pintype "passive"))
      (node (ref "R118") (pin "1") (pinfunction "1_1") (pintype "passive"))
      (node (ref "R98") (pin "1") (pinfunction "1_1") (pintype "passive"))
      (node (ref "XT2") (pin "2") (pinfunction "GND_2") (pintype "passive"))
      (node (ref "XT3") (pin "2") (pinfunction "GND_2") (pintype "passive"))
      (node (ref "XT4") (pin "2") (pinfunction "GND_2") (pintype "passive"))
      (node (ref "XT5") (pin "2") (pinfunction "GND_2") (pintype "passive"))
      (node (ref "XT5") (pin "4") (pinfunction "GND_4") (pintype "passive"))
    )
    (net (code "27") (name "Net-(C181-Pad1)") (class "Default")
      (node (ref "C181") (pin "1") (pinfunction "1_1") (pintype "passive"))
      (node (ref "C182") (pin "2") (pinfunction "2_2") (pintype "passive"))
      (node (ref "R98") (pin "2") (pinfunction "2_2") (pintype "passive"))
    )
    (net (code "28") (name "Net-(C181-Pad2)") (class "Default")
      (node (ref "C181") (pin "2") (pinfunction "2_2") (pintype "passive"))
      (node (ref "R103") (pin "1") (pinfunction "1_1") (pintype "passive"))
      (node (ref "R104") (pin "1") (pinfunction "1_1") (pintype "passive"))
      (node (ref "R105") (pin "2") (pinfunction "2_2") (pintype "passive"))
      (node (ref "R106") (pin "1") (pinfunction "1_1") (pintype "passive"))
      (node (ref "R107") (pin "1") (pinfunction "1_1") (pintype "passive"))
      (node (ref "R96") (pin "1") (pinfunction "1_1") (pintype "passive"))
    )
    (net (code "29") (name "Net-(C199-Pad2)") (class "Default")
      (node (ref "C199") (pin "2") (pinfunction "2_2") (pintype "passive"))
      (node (ref "FR50") (pin "2") (pinfunction "2_2") (pintype "passive"))
      (node (ref "R108") (pin "2") (pinfunction "2_2") (pintype "passive"))
    )
    (net (code "30") (name "Net-(C201-Pad2)") (class "Default")
      (node (ref "C201") (pin "2") (pinfunction "2_2") (pintype "passive"))
      (node (ref "C202") (pin "1") (pinfunction "1_1") (pintype "passive"))
      (node (ref "R109") (pin "2") (pinfunction "2_2") (pintype "passive"))
    )
    (net (code "31") (name "Net-(C204-Pad2)") (class "Default")
      (node (ref "C204") (pin "2") (pinfunction "2_2") (pintype "passive"))
      (node (ref "C205") (pin "1") (pinfunction "1_1") (pintype "passive"))
      (node (ref "C206") (pin "1") (pinfunction "1_1") (pintype "passive"))
      (node (ref "FR51") (pin "2") (pinfunction "2_2") (pintype "passive"))
      (node (ref "IC16") (pin "6") (pinfunction "AVdd_6") (pintype "passive"))
      (node (ref "IC16") (pin "7") (pinfunction "AVdd_7") (pintype "passive"))
    )
    (net (code "32") (name "Net-(C211-Pad1)") (class "Default")
      (node (ref "C211") (pin "1") (pinfunction "1_1") (pintype "passive"))
      (node (ref "C212") (pin "2") (pinfunction "2_2") (pintype "passive"))
      (node (ref "R114") (pin "2") (pinfunction "2_2") (pintype "passive"))
    )
    (net (code "33") (name "Net-(C213-Pad2)") (class "Default")
      (node (ref "C213") (pin "2") (pinfunction "2_2") (pintype "passive"))
      (node (ref "R112") (pin "2") (pinfunction "2_2") (pintype "passive"))
      (node (ref "R113") (pin "1") (pinfunction "1_1") (pintype "passive"))
    )
    (net (code "34") (name "Net-(C214-Pad1)") (class "Default")
      (node (ref "C214") (pin "1") (pinfunction "1_1") (pintype "passive"))
      (node (ref "R118") (pin "2") (pinfunction "2_2") (pintype "passive"))
    )
    (net (code "35") (name "Net-(IC13-CLKin)") (class "Default")
      (node (ref "C182") (pin "1") (pinfunction "1_1") (pintype "passive"))
      (node (ref "IC13") (pin "21") (pinfunction "CLKin_21") (pintype "passive"))
    )
    (net (code "36") (name "Net-(IC13-CLKin*)") (class "Default")
      (node (ref "C183") (pin "2") (pinfunction "2_2") (pintype "passive"))
      (node (ref "IC13") (pin "20") (pinfunction "CLKin*_20") (pintype "passive"))
    )
    (net (code "37") (name "Net-(IC13-CLKout0)") (class "Default")
      (node (ref "IC13") (pin "3") (pinfunction "CLKout0_3") (pintype "passive"))
      (node (ref "R97") (pin "2") (pinfunction "2_2") (pintype "passive"))
    )
    (net (code "38") (name "Net-(IC13-CLKout1)") (class "Default")
      (node (ref "IC13") (pin "5") (pinfunction "CLKout1_5") (pintype "passive"))
      (node (ref "R101") (pin "2") (pinfunction "2_2") (pintype "passive"))
    )
    (net (code "39") (name "Net-(IC13-OE)") (class "Default")
      (node (ref "IC13") (pin "24") (pinfunction "OE_24") (pintype "passive"))
      (node (ref "R99") (pin "2") (pinfunction "2_2") (pintype "passive"))
    )
    (net (code "40") (name "Net-(IC14-C)") (class "Default")
      (node (ref "IC14") (pin "1") (pinfunction "C_1") (pintype "passive"))
      (node (ref "R102") (pin "1") (pinfunction "1_1") (pintype "passive"))
    )
    (net (code "41") (name "Net-(IC14-CLR)") (class "Default")
      (node (ref "C188") (pin "2") (pinfunction "2_2") (pintype "passive"))
      (node (ref "IC14") (pin "6") (pinfunction "CLR_6") (pintype "passive"))
      (node (ref "IC14") (pin "7") (pinfunction "PR_7") (pintype "passive"))
      (node (ref "IC14") (pin "8") (pinfunction "VCC_8") (pintype "passive"))
      (node (ref "R100") (pin "2") (pinfunction "2_2") (pintype "passive"))
    )
    (net (code "42") (name "Net-(IC14-D)") (class "Default")
      (node (ref "IC14") (pin "2") (pinfunction "D_2") (pintype "passive"))
      (node (ref "IC14") (pin "3") (pinfunction "Qn_3") (pintype "passive"))
      (node (ref "R104") (pin "2") (pinfunction "2_2") (pintype "passive"))
    )
    (net (code "43") (name "Net-(IC14-Qp)") (class "Default")
      (node (ref "IC14") (pin "5") (pinfunction "Qp_5") (pintype "passive"))
      (node (ref "R103") (pin "2") (pinfunction "2_2") (pintype "passive"))
    )
    (net (code "44") (name "Net-(IC15-VDD)") (class "Default")
      (node (ref "C200") (pin "1") (pinfunction "1_1") (pintype "passive"))
      (node (ref "FR52") (pin "2") (pinfunction "2_2") (pintype "passive"))
      (node (ref "IC15") (pin "4") (pinfunction "VDD_4") (pintype "power_in"))
    )
    (net (code "45") (name "Net-(IC15-VOUT)") (class "Default")
      (node (ref "FR50") (pin "1") (pinfunction "1_1") (pintype "passive"))
      (node (ref "IC15") (pin "6") (pinfunction "VOUT_6") (pintype "tri_state"))
    )
    (net (code "46") (name "Net-(IC16-CE)") (class "Default")
      (node (ref "IC16") (pin "11") (pinfunction "CE_11") (pintype "passive"))
      (node (ref "R111") (pin "1") (pinfunction "1_1") (pintype "passive"))
    )
    (net (code "47") (name "Net-(IC16-CLK)") (class "Default")
      (node (ref "C220") (pin "2") (pinfunction "2_2") (pintype "passive"))
      (node (ref "IC16") (pin "12") (pinfunction "CLK_12") (pintype "passive"))
      (node (ref "R119") (pin "2") (pinfunction "2_2") (pintype "passive"))
    )
    (net (code "48") (name "Net-(IC16-CP)") (class "Default")
      (node (ref "C214") (pin "2") (pinfunction "2_2") (pintype "passive"))
      (node (ref "C215") (pin "2") (pinfunction "2_2") (pintype "passive"))
      (node (ref "IC16") (pin "20") (pinfunction "CP_20") (pintype "passive"))
      (node (ref "R112") (pin "1") (pinfunction "1_1") (pintype "passive"))
    )
    (net (code "49") (name "Net-(IC16-DATA)") (class "Default")
      (node (ref "IC16") (pin "13") (pinfunction "DATA_13") (pintype "passive"))
      (node (ref "R120") (pin "2") (pinfunction "2_2") (pintype "passive"))
    )
    (net (code "50") (name "Net-(IC16-LE)") (class "Default")
      (node (ref "IC16") (pin "14") (pinfunction "LE_14") (pintype "passive"))
      (node (ref "R121") (pin "2") (pinfunction "2_2") (pintype "passive"))
    )
    (net (code "51") (name "Net-(IC16-RFin)") (class "Default")
      (node (ref "C211") (pin "2") (pinfunction "2_2") (pintype "passive"))
      (node (ref "IC16") (pin "8") (pinfunction "RFin_8") (pintype "passive"))
    )
    (net (code "52") (name "Net-(IC16-RFinA)") (class "Default")
      (node (ref "C201") (pin "1") (pinfunction "1_1") (pintype "passive"))
      (node (ref "IC16") (pin "5") (pinfunction "RFinA_5") (pintype "passive"))
    )
    (net (code "53") (name "Net-(IC16-RFinB)") (class "Default")
      (node (ref "C216") (pin "1") (pinfunction "1_1") (pintype "passive"))
      (node (ref "IC16") (pin "4") (pinfunction "RFinB_4") (pintype "passive"))
    )
    (net (code "54") (name "Net-(IC16-Rset)") (class "Default")
      (node (ref "IC16") (pin "19") (pinfunction "Rset_19") (pintype "passive"))
      (node (ref "R117") (pin "1") (pinfunction "1_1") (pintype "passive"))
    )
    (net (code "55") (name "Net-(IC16-Vp)") (class "Default")
      (node (ref "C209") (pin "2") (pinfunction "2_2") (pintype "passive"))
      (node (ref "C210") (pin "1") (pinfunction "1_1") (pintype "passive"))
      (node (ref "IC16") (pin "18") (pinfunction "Vp_18") (pintype "passive"))
      (node (ref "R110") (pin "1") (pinfunction "1_1") (pintype "passive"))
    )
    (net (code "56") (name "Net-(XT2-OUT)") (class "Default")
      (node (ref "R102") (pin "2") (pinfunction "2_2") (pintype "passive"))
      (node (ref "R96") (pin "2") (pinfunction "2_2") (pintype "passive"))
      (node (ref "XT2") (pin "4") (pinfunction "OUT_4") (pintype "passive"))
      (node (ref "XT3") (pin "3") (pinfunction "OUT_3") (pintype "passive"))
      (node (ref "XT4") (pin "3") (pinfunction "OUT_3") (pintype "passive"))
    )
    (net (code "57") (name "Net-(XT2-TRI-ST.)") (class "Default")
      (node (ref "R95") (pin "1") (pinfunction "1_1") (pintype "passive"))
      (node (ref "XT2") (pin "6") (pinfunction "TRI-ST._6") (pintype "passive"))
    )
    (net (code "58") (name "Net-(XT2-VDD)") (class "Default")
      (node (ref "C186") (pin "2") (pinfunction "2_2") (pintype "passive"))
      (node (ref "C187") (pin "2") (pinfunction "2_2") (pintype "passive"))
      (node (ref "FR47") (pin "1") (pinfunction "1_1") (pintype "passive"))
      (node (ref "R95") (pin "2") (pinfunction "2_2") (pintype "passive"))
      (node (ref "XT2") (pin "5") (pinfunction "VDD_5") (pintype "passive"))
      (node (ref "XT3") (pin "4") (pinfunction "VDD_4") (pintype "passive"))
      (node (ref "XT4") (pin "4") (pinfunction "VDD_4") (pintype "passive"))
    )
    (net (code "59") (name "VCC1P8") (class "Default")
      (node (ref "C222") (pin "1") (pinfunction "1_1") (pintype "passive"))
      (node (ref "C223") (pin "1") (pinfunction "1_1") (pintype "passive"))
      (node (ref "C224") (pin "1") (pinfunction "1_1") (pintype "passive"))
      (node (ref "IC17") (pin "10") (pinfunction "VDDOB_10") (pintype "passive"))
      (node (ref "IC17") (pin "11") (pinfunction "VDDOA_11") (pintype "passive"))
      (node (ref "IC17") (pin "14") (pinfunction "VDDOD_14") (pintype "passive"))
    )
    (net (code "60") (name "VCC1P8_LMS") (class "Default")
      (node (ref "FR48") (pin "1") (pinfunction "1_1") (pintype "passive"))
    )
    (net (code "61") (name "VCC3P3_CLK") (class "Default")
      (node (ref "C203") (pin "2") (pinfunction "2_2") (pintype "passive"))
      (node (ref "C207") (pin "1") (pinfunction "1_1") (pintype "passive"))
      (node (ref "C208") (pin "1") (pinfunction "1_1") (pintype "passive"))
      (node (ref "FR47") (pin "2") (pinfunction "2_2") (pintype "passive"))
      (node (ref "FR51") (pin "1") (pinfunction "1_1") (pintype "passive"))
      (node (ref "FR52") (pin "1") (pinfunction "1_1") (pintype "passive"))
      (node (ref "IC13") (pin "23") (pinfunction "Vdd_23") (pintype "passive"))
      (node (ref "IC13") (pin "8") (pinfunction "Vdd_8") (pintype "passive"))
      (node (ref "IC16") (pin "16") (pinfunction "DVdd_16") (pintype "passive"))
      (node (ref "IC16") (pin "17") (pinfunction "DVdd_17") (pintype "passive"))
      (node (ref "R100") (pin "1") (pinfunction "1_1") (pintype "passive"))
      (node (ref "R110") (pin "2") (pinfunction "2_2") (pintype "passive"))
      (node (ref "R111") (pin "2") (pinfunction "2_2") (pintype "passive"))
      (node (ref "R115") (pin "2") (pinfunction "2_2") (pintype "passive"))
      (node (ref "R99") (pin "1") (pinfunction "1_1") (pintype "passive"))
    )
    (net (code "62") (name "VCC3P3_SI") (class "Default")
      (node (ref "C217") (pin "1") (pinfunction "1_1") (pintype "passive"))
      (node (ref "C218") (pin "1") (pinfunction "1_1") (pintype "passive"))
      (node (ref "IC17") (pin "18") (pinfunction "VDDOC_18") (pintype "passive"))
      (node (ref "IC17") (pin "20") (pinfunction "VDD_20") (pintype "passive"))
      (node (ref "R115") (pin "1") (pinfunction "1_1") (pintype "passive"))
    )
    (net (code "63") (name "VDIO_LMS_FPGA") (class "Default")
      (node (ref "FR49") (pin "1") (pinfunction "1_1") (pintype "passive"))
    )
    (net (code "64") (name "VDIO_LMS_LMK") (class "Default")
      (node (ref "C190") (pin "2") (pinfunction "2_2") (pintype "passive"))
      (node (ref "C191") (pin "2") (pinfunction "2_2") (pintype "passive"))
      (node (ref "C192") (pin "2") (pinfunction "2_2") (pintype "passive"))
      (node (ref "C193") (pin "2") (pinfunction "2_2") (pintype "passive"))
      (node (ref "C194") (pin "2") (pinfunction "2_2") (pintype "passive"))
      (node (ref "C198") (pin "2") (pinfunction "2_2") (pintype "passive"))
      (node (ref "FR49") (pin "2") (pinfunction "2_2") (pintype "passive"))
      (node (ref "IC13") (pin "14") (pinfunction "Vddo_14") (pintype "passive"))
      (node (ref "IC13") (pin "18") (pinfunction "Vddo_18") (pintype "passive"))
    )
    (net (code "65") (name "unconnected-(IC13-CLKout4-Pad17)") (class "Default")
      (node (ref "IC13") (pin "17") (pinfunction "CLKout4_17") (pintype "passive+no_connect"))
    )
    (net (code "66") (name "unconnected-(IC13-OSCin-Pad9)") (class "Default")
      (node (ref "IC13") (pin "9") (pinfunction "OSCin_9") (pintype "passive+no_connect"))
    )
    (net (code "67") (name "unconnected-(IC13-OSCout-Pad10)") (class "Default")
      (node (ref "IC13") (pin "10") (pinfunction "OSCout_10") (pintype "passive+no_connect"))
    )
    (net (code "68") (name "unconnected-(IC17-INTR-Pad3)") (class "Default")
      (node (ref "IC17") (pin "3") (pinfunction "INTR_3") (pintype "passive+no_connect"))
    )
    (net (code "69") (name "unconnected-(XT2-T.S.-Pad3)") (class "Default")
      (node (ref "XT2") (pin "3") (pinfunction "T.S._3") (pintype "passive+no_connect"))
    )
  )
)
